# MOTORES.net
KiCad netlist of a schematic drawn in Altium Designer
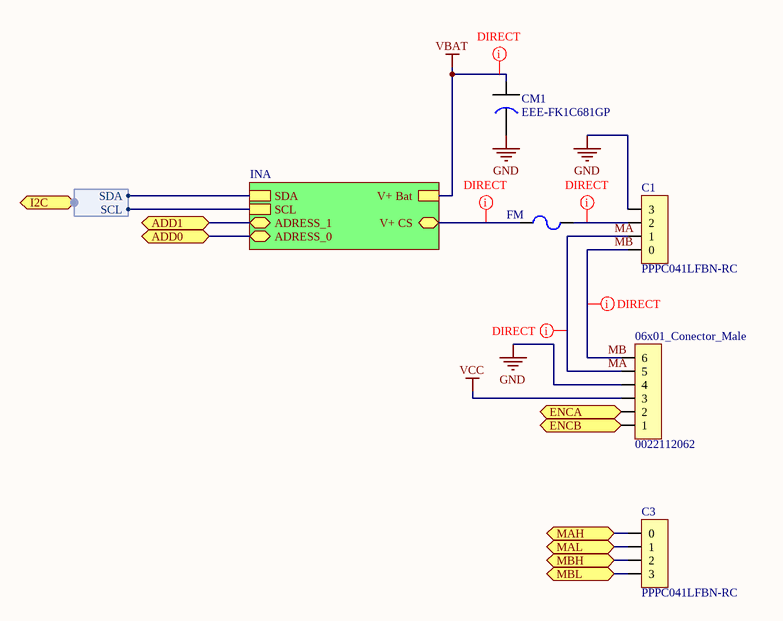
[diagram p0: MOTORES.SchDoc]

(export (version "E")
  (design (tool "Eeschema 10.0.6"))
  (components
    (comp (ref "06x01_Conector_Male")
      (value "0022112062")
      (footprint "06x01_Conector_Male")
      (description "CONN HEADER 6POS .100 VERT GOLD")
      (libsource (lib "Schlib1") (part "06x01_Conector_Male"))
    )
    (comp (ref "C1")
      (value "PPPC041LFBN-RC")
      (footprint "04x01_Conector_Female")
      (description "4 Position Header Connector 0.100\" (2.54mm) Through Hole Gold")
      (libsource (lib "") (part "04x01_Conector_Female-SCH_1"))
    )
    (comp (ref "C3")
      (value "PPPC041LFBN-RC")
      (footprint "04x01_Conector_Female")
      (description "4 Position Header Connector 0.100\" (2.54mm) Through Hole Gold")
      (libsource (lib "Schlib1") (part "04x01_Conector_Female-SCH"))
    )
    (comp (ref "CM1")
      (value "EEE-FK1C681GP")
      (footprint "EEE-FK1C681GP")
      (description "Aluminum Electrolytic Capacitors - SMD Al Lytic Cap SMT FK Series 105C")
      (libsource (lib "Schlib1") (part "CAP AL 680UF/16V"))
    )
    (comp (ref "FM")
      (value "MF-MSMF250/16X")
      (footprint "RESC4632X16N")
      (description "PTC RESETTABLE .30A 30V 1812")
      (libsource (lib "IMBEL") (part "MF-MSMF250/16X-01.A.1"))
    )
  )
  (nets
    (net (code "4") (name "/ENCA") (class "Default")
      (node (ref "06x01_Conector_Male") (pin "2") (pinfunction "2_2") (pintype "passive"))
    )
    (net (code "5") (name "/ENCB") (class "Default")
      (node (ref "06x01_Conector_Male") (pin "1") (pinfunction "1_1") (pintype "passive"))
    )
    (net (code "6") (name "/MA") (class "Default")
      (node (ref "06x01_Conector_Male") (pin "5") (pinfunction "5_5") (pintype "passive"))
      (node (ref "C1") (pin "1") (pinfunction "1_1") (pintype "passive"))
    )
    (net (code "7") (name "/MAH") (class "Default")
      (node (ref "C3") (pin "0") (pinfunction "0_0") (pintype "passive"))
    )
    (net (code "8") (name "/MAL") (class "Default")
      (node (ref "C3") (pin "1") (pinfunction "1_1") (pintype "passive"))
    )
    (net (code "9") (name "/MB") (class "Default")
      (node (ref "06x01_Conector_Male") (pin "6") (pinfunction "6_6") (pintype "passive"))
      (node (ref "C1") (pin "0") (pinfunction "0_0") (pintype "passive"))
    )
    (net (code "10") (name "/MBH") (class "Default")
      (node (ref "C3") (pin "2") (pinfunction "2_2") (pintype "passive"))
    )
    (net (code "11") (name "/MBL") (class "Default")
      (node (ref "C3") (pin "3") (pinfunction "3_3") (pintype "passive"))
    )
    (net (code "14") (name "/V+ CS") (class "Default")
      (node (ref "FM") (pin "2") (pinfunction "2_2") (pintype "passive"))
    )
    (net (code "16") (name "GND") (class "Default")
      (node (ref "06x01_Conector_Male") (pin "4") (pinfunction "4_4") (pintype "passive"))
      (node (ref "C1") (pin "3") (pinfunction "3_3") (pintype "passive"))
      (node (ref "CM1") (pin "2") (pinfunction "2_2") (pintype "passive"))
    )
    (net (code "17") (name "Net-(C1-Pad2)") (class "Default")
      (node (ref "C1") (pin "2") (pinfunction "2_2") (pintype "passive"))
      (node (ref "FM") (pin "1") (pinfunction "1_1") (pintype "passive"))
    )
    (net (code "18") (name "VBAT") (class "Default")
      (node (ref "CM1") (pin "1") (pinfunction "1_1") (pintype "passive"))
    )
    (net (code "19") (name "VCC") (class "Default")
      (node (ref "06x01_Conector_Male") (pin "3") (pinfunction "3_3") (pintype "passive"))
    )
  )
)
